# Net500.net
KiCad netlist of a schematic drawn in Altium Designer
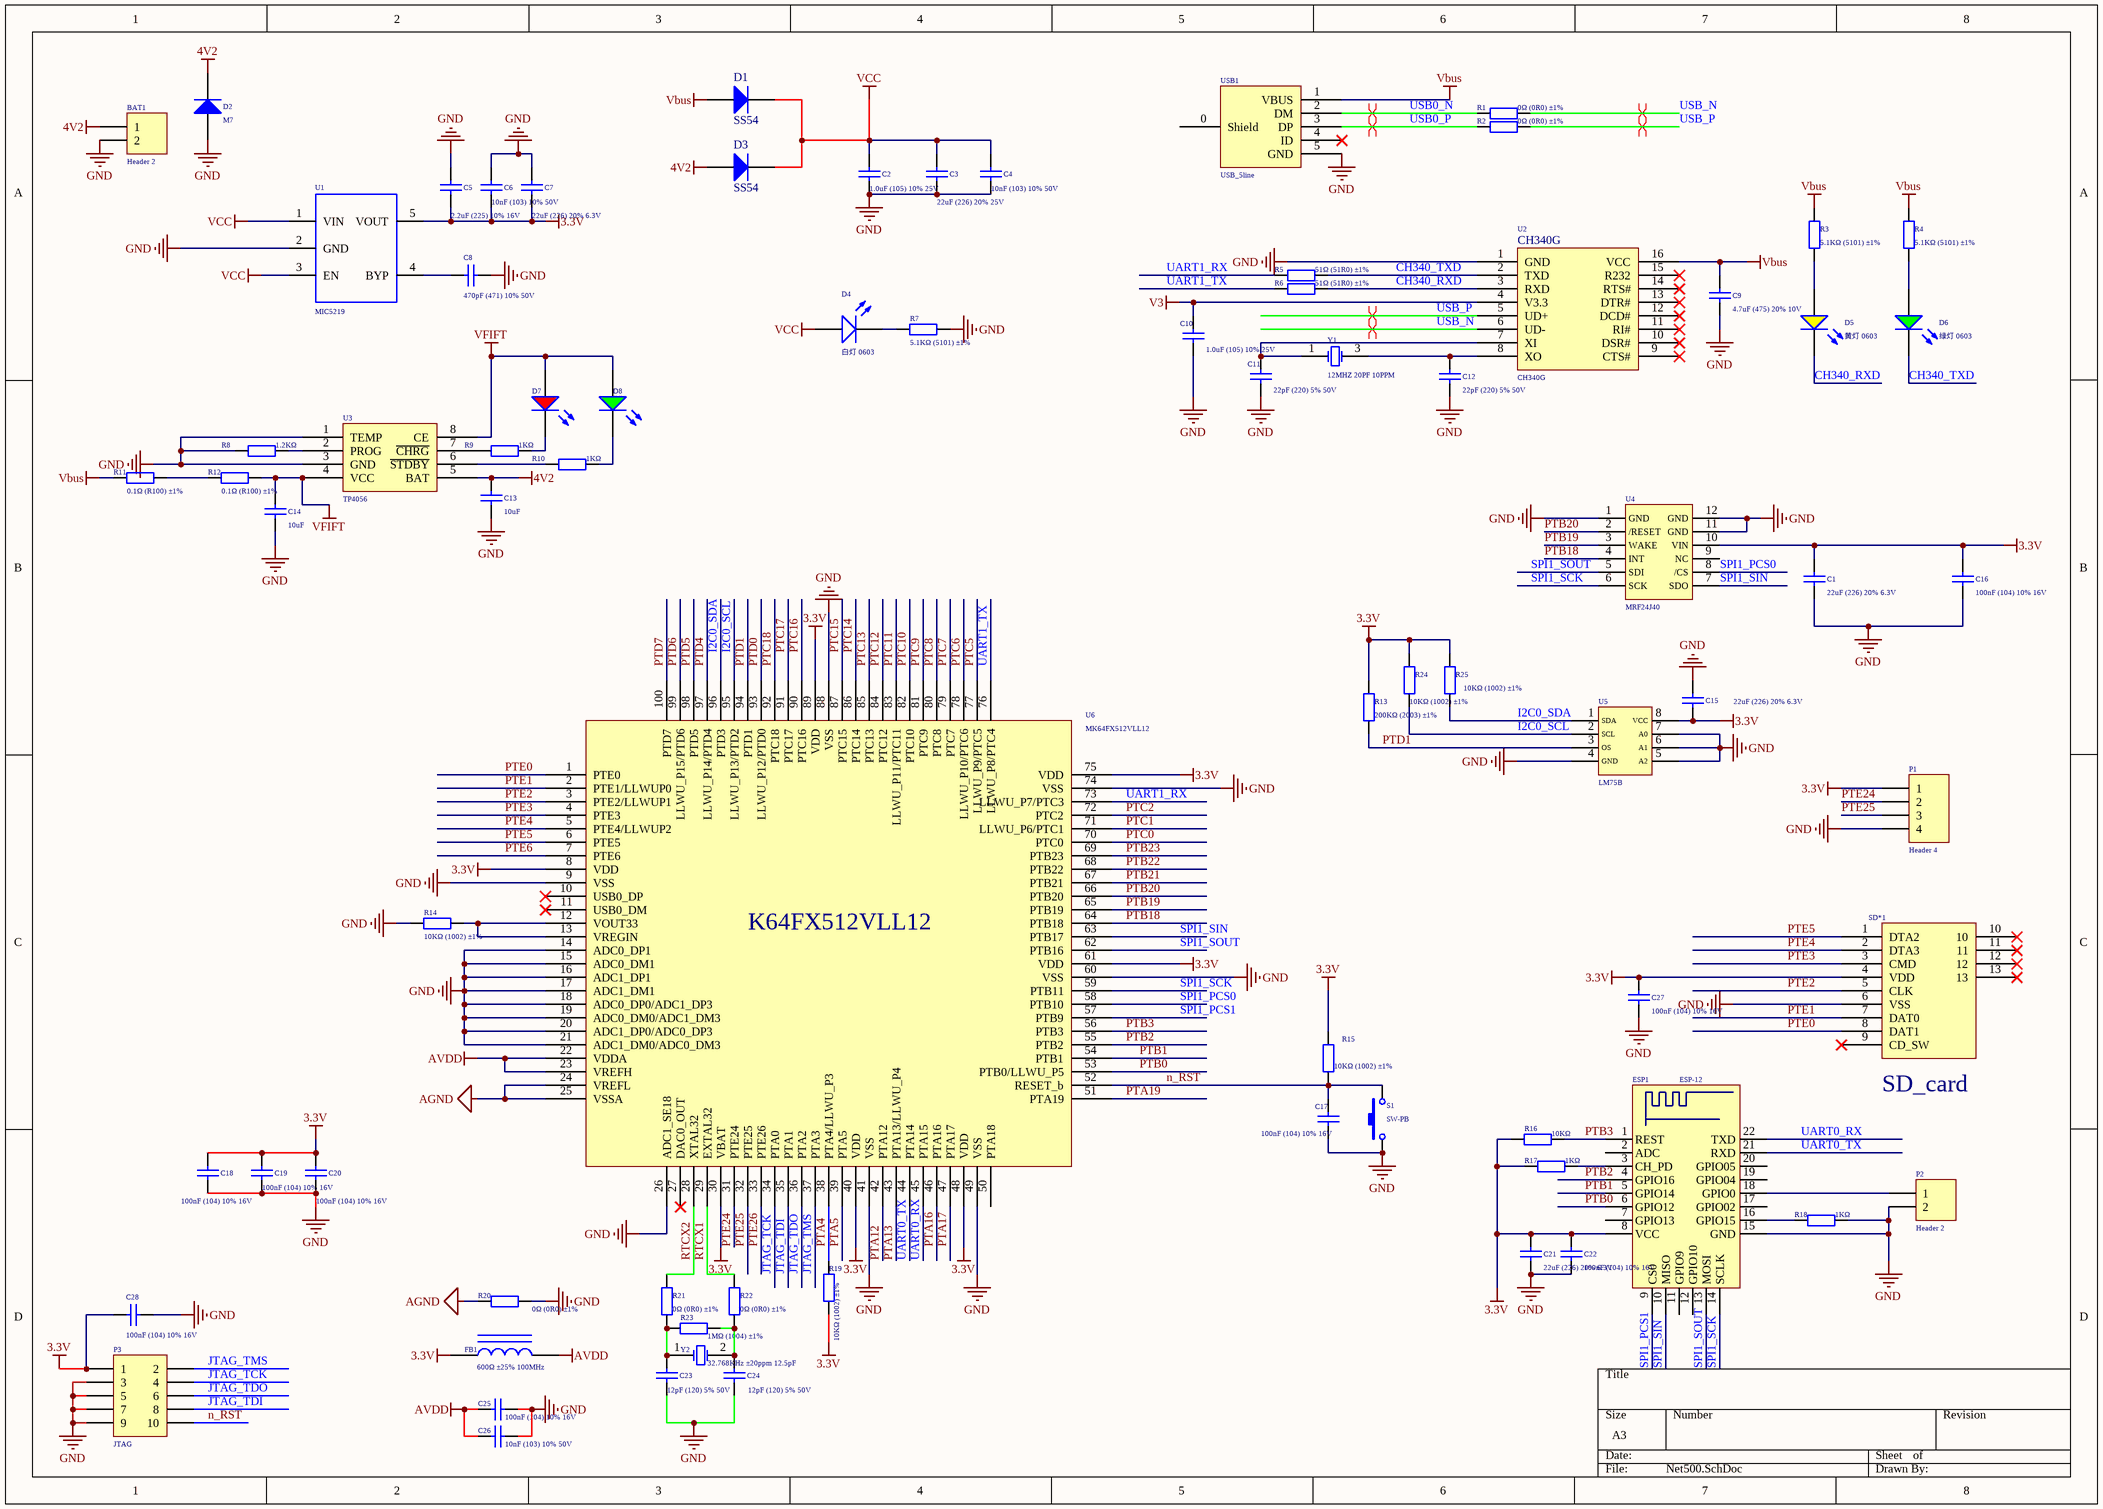
[diagram p0: Net500.SchDoc]

(export (version "E")
  (design (tool "Eeschema 10.0.6"))
  (components
    (comp (ref "BAT1")
      (value "Header 2")
      (footprint "HDR1X2")
      (description "Header, 2-Pin")
      (fields (field (name "PUBLISHER") "Altium Limited"))
      (libsource (lib "Sparks") (part "Header 2"))
    )
    (comp (ref "C1")
      (value "22uF (226) 20% 6.3V")
      (footprint "0603_C")
      (description "贴片电容")
      (libsource (lib "Miscellaneous Devices LC") (part "0603 22uF (226) 20% 6.3V"))
    )
    (comp (ref "C2")
      (value "1.0uF (105) 10% 25V")
      (footprint "0402_C")
      (description "贴片电容")
      (libsource (lib "Miscellaneous Devices LC") (part "0402 1.0uF (105) 10% 25V"))
    )
    (comp (ref "C3")
      (value "22uF (226) 20% 25V")
      (footprint "0805_C")
      (description "贴片电容")
      (libsource (lib "Miscellaneous Devices LC") (part "0805 22uF (226) 20% 25V"))
    )
    (comp (ref "C4")
      (value "10nF (103) 10% 50V")
      (footprint "0402_C")
      (description "贴片电容")
      (libsource (lib "Miscellaneous Devices LC") (part "0402 10nF (103) 10% 50V"))
    )
    (comp (ref "C5")
      (value "2.2uF (225) 10% 16V")
      (footprint "0603_C")
      (description "贴片电容")
      (libsource (lib "Miscellaneous Devices LC") (part "0603 2.2uF (225) 10% 16V"))
    )
    (comp (ref "C6")
      (value "10nF (103) 10% 50V")
      (footprint "0402_C")
      (description "贴片电容")
      (libsource (lib "Miscellaneous Devices LC") (part "0402 10nF (103) 10% 50V"))
    )
    (comp (ref "C7")
      (value "22uF (226) 20% 6.3V")
      (footprint "0603_C")
      (description "贴片电容")
      (libsource (lib "Miscellaneous Devices LC") (part "0603 22uF (226) 20% 6.3V"))
    )
    (comp (ref "C8")
      (value "470pF (471) 10% 50V")
      (footprint "0402_C")
      (description "贴片电容")
      (libsource (lib "Miscellaneous Devices LC") (part "0402 470pF (471) 10% 50V"))
    )
    (comp (ref "C9")
      (value "4.7uF (475) 20% 10V")
      (footprint "0402_C")
      (description "贴片电容")
      (libsource (lib "Miscellaneous Devices LC") (part "0402 4.7uF (475) 20% 10V"))
    )
    (comp (ref "C10")
      (value "1.0uF (105) 10% 25V")
      (footprint "0402_C")
      (description "贴片电容")
      (libsource (lib "Miscellaneous Devices LC") (part "0402 1.0uF (105) 10% 25V"))
    )
    (comp (ref "C11")
      (value "22pF (220) 5% 50V")
      (footprint "0402_C")
      (description "贴片电容")
      (libsource (lib "Miscellaneous Devices LC") (part "0402 22pF (220) 5% 50V"))
    )
    (comp (ref "C12")
      (value "22pF (220) 5% 50V")
      (footprint "0402_C")
      (description "贴片电容")
      (libsource (lib "Miscellaneous Devices LC") (part "0402 22pF (220) 5% 50V"))
    )
    (comp (ref "C13")
      (value "10uF")
      (footprint "0402_C")
      (description "贴片电容")
      (libsource (lib "Cap") (part "0402 10uF (106) 20% 6.3V"))
    )
    (comp (ref "C14")
      (value "10uF")
      (footprint "0402_C")
      (description "贴片电容")
      (libsource (lib "Cap") (part "0402 10uF (106) 20% 6.3V"))
    )
    (comp (ref "C15")
      (value "22uF (226) 20% 6.3V")
      (footprint "0603_C")
      (description "贴片电容")
      (libsource (lib "Miscellaneous Devices LC") (part "0603 22uF (226) 20% 6.3V"))
    )
    (comp (ref "C16")
      (value "100nF (104) 10% 16V")
      (footprint "0402_C")
      (description "贴片电容")
      (libsource (lib "Miscellaneous Devices LC") (part "0402 100nF (104) 10% 16V"))
    )
    (comp (ref "C17")
      (value "100nF (104) 10% 16V")
      (footprint "0402_C")
      (description "贴片电容")
      (libsource (lib "Miscellaneous Devices LC") (part "0402 100nF (104) 10% 16V"))
    )
    (comp (ref "C18")
      (value "100nF (104) 10% 16V")
      (footprint "0402_C")
      (description "贴片电容")
      (libsource (lib "Miscellaneous Devices LC") (part "0402 100nF (104) 10% 16V"))
    )
    (comp (ref "C19")
      (value "100nF (104) 10% 16V")
      (footprint "0402_C")
      (description "贴片电容")
      (libsource (lib "Miscellaneous Devices LC") (part "0402 100nF (104) 10% 16V"))
    )
    (comp (ref "C20")
      (value "100nF (104) 10% 16V")
      (footprint "0402_C")
      (description "贴片电容")
      (libsource (lib "Miscellaneous Devices LC") (part "0402 100nF (104) 10% 16V"))
    )
    (comp (ref "C21")
      (value "22uF (226) 20% 6.3V")
      (footprint "0603_C")
      (description "贴片电容")
      (libsource (lib "Miscellaneous Devices LC") (part "0603 22uF (226) 20% 6.3V"))
    )
    (comp (ref "C22")
      (value "100nF (104) 10% 16V")
      (footprint "0402_C")
      (description "贴片电容")
      (libsource (lib "Miscellaneous Devices LC") (part "0402 100nF (104) 10% 16V"))
    )
    (comp (ref "C23")
      (value "12pF (120) 5% 50V")
      (footprint "0402_C")
      (description "贴片电容")
      (libsource (lib "Miscellaneous Devices LC") (part "0402 12pF (120) 5% 50V"))
    )
    (comp (ref "C24")
      (value "12pF (120) 5% 50V")
      (footprint "0402_C")
      (description "贴片电容")
      (libsource (lib "Miscellaneous Devices LC") (part "0402 12pF (120) 5% 50V"))
    )
    (comp (ref "C25")
      (value "100nF (104) 10% 16V")
      (footprint "0402_C")
      (description "贴片电容")
      (libsource (lib "Miscellaneous Devices LC") (part "0402 100nF (104) 10% 16V"))
    )
    (comp (ref "C26")
      (value "10nF (103) 10% 50V")
      (footprint "0402_C")
      (description "贴片电容")
      (libsource (lib "Miscellaneous Devices LC") (part "0402 10nF (103) 10% 50V"))
    )
    (comp (ref "C27")
      (value "100nF (104) 10% 16V")
      (footprint "0402_C")
      (description "贴片电容")
      (libsource (lib "Miscellaneous Devices LC") (part "0402 100nF (104) 10% 16V"))
    )
    (comp (ref "C28")
      (value "100nF (104) 10% 16V")
      (footprint "0402_C")
      (description "贴片电容")
      (libsource (lib "Miscellaneous Devices LC") (part "0402 100nF (104) 10% 16V"))
    )
    (comp (ref "D1")
      (value "SS54")
      (footprint "SMA(DO-214AC)_S1")
      (description "二极管")
      (libsource (lib "Miscellaneous Devices LC") (part "SMA(DO-214AC) SS54"))
    )
    (comp (ref "D2")
      (value "M7")
      (footprint "SMA(DO-214AC)_S1")
      (description "二极管")
      (libsource (lib "Miscellaneous Devices LC") (part "SMA(DO-214AC) M7"))
    )
    (comp (ref "D3")
      (value "SS54")
      (footprint "SMA(DO-214AC)_S1")
      (description "二极管")
      (libsource (lib "Miscellaneous Devices LC") (part "SMA(DO-214AC) SS54"))
    )
    (comp (ref "D4")
      (value "白灯 0603")
      (footprint "0603_LED_S1")
      (description "发光二极管")
      (libsource (lib "Miscellaneous Devices LC") (part "0603 白灯"))
    )
    (comp (ref "D5")
      (value "黄灯 0603")
      (footprint "0603_LED_S1")
      (description "发光二极管")
      (libsource (lib "Miscellaneous Devices LC") (part "0603 黄灯"))
    )
    (comp (ref "D6")
      (value "绿灯 0603")
      (footprint "0603_LED_S1")
      (description "发光二极管")
      (libsource (lib "Miscellaneous Devices LC") (part "0603 绿灯"))
    )
    (comp (ref "D7")
      (value "红灯 0603")
      (footprint "0603_LED_S1")
      (description "发光二极管")
      (libsource (lib "LED") (part "0603 红灯"))
    )
    (comp (ref "D8")
      (value "绿灯 0603")
      (footprint "0603_LED_S1")
      (description "发光二极管")
      (libsource (lib "LED") (part "0603 绿灯"))
    )
    (comp (ref "ESP1") (value "ESP-12") (footprint "ESP-12") (libsource (lib "2号库") (part "ESP-12")))
    (comp (ref "FB1")
      (value "600Ω ±25% 100MHz")
      (footprint "0805_L")
      (description "贴片磁珠")
      (libsource (lib "Miscellaneous Devices LC") (part "0805 600Ω 25% 100MHz"))
    )
    (comp (ref "P1")
      (value "Header 4")
      (footprint "HDR1X4")
      (description "Header, 4-Pin")
      (fields (field (name "PUBLISHER") "Altium Limited"))
      (libsource (lib "Sparks") (part "Header 4"))
    )
    (comp (ref "P2")
      (value "Header 2")
      (footprint "HDR1X2")
      (description "Header, 2-Pin")
      (fields (field (name "PUBLISHER") "Altium Limited"))
      (libsource (lib "Sparks") (part "Header 2"))
    )
    (comp (ref "P3")
      (value "JTAG")
      (footprint "MHDR2X5")
      (description "Header, 5-Pin, Dual row")
      (fields (field (name "PUBLISHER") "Altium Limited"))
      (libsource (lib "Sparks") (part "Header 5X2"))
    )
    (comp (ref "R1")
      (value "0Ω (0R0) ±1%")
      (footprint "0402_R")
      (description "贴片电阻")
      (libsource (lib "") (part "0402 0Ω (0R0) 1%_1"))
    )
    (comp (ref "R2")
      (value "0Ω (0R0) ±1%")
      (footprint "0402_R")
      (description "贴片电阻")
      (libsource (lib "") (part "0402 0Ω (0R0) 1%_1"))
    )
    (comp (ref "R3")
      (value "5.1KΩ (5101) ±1%")
      (footprint "0402_R")
      (description "贴片电阻")
      (libsource (lib "Miscellaneous Devices LC") (part "0402 5.1KΩ (5101) 1%"))
    )
    (comp (ref "R4")
      (value "5.1KΩ (5101) ±1%")
      (footprint "0402_R")
      (description "贴片电阻")
      (libsource (lib "Miscellaneous Devices LC") (part "0402 5.1KΩ (5101) 1%"))
    )
    (comp (ref "R5")
      (value "51Ω (51R0) ±1%")
      (footprint "0402_R")
      (description "贴片电阻")
      (libsource (lib "Miscellaneous Devices LC") (part "0402 51Ω (51R0) 1%"))
    )
    (comp (ref "R6")
      (value "51Ω (51R0) ±1%")
      (footprint "0402_R")
      (description "贴片电阻")
      (libsource (lib "Miscellaneous Devices LC") (part "0402 51Ω (51R0) 1%"))
    )
    (comp (ref "R7")
      (value "5.1KΩ (5101) ±1%")
      (footprint "0402_R")
      (description "贴片电阻")
      (libsource (lib "") (part "0402 5.1KΩ (5101) 1%_1"))
    )
    (comp (ref "R8")
      (value "1.2KΩ")
      (footprint "0402_R")
      (description "贴片电阻")
      (libsource (lib "RES") (part "0402 1.2KΩ (1201) 1%"))
    )
    (comp (ref "R9")
      (value "1KΩ")
      (footprint "0402_R")
      (description "贴片电阻")
      (libsource (lib "RES") (part "0402 1KΩ (1001) 1%"))
    )
    (comp (ref "R10")
      (value "1KΩ")
      (footprint "0402_R")
      (description "贴片电阻")
      (libsource (lib "RES") (part "0402 1KΩ (1001) 1%"))
    )
    (comp (ref "R11")
      (value "0.1Ω (R100) ±1%")
      (footprint "1206_R")
      (description "贴片电阻")
      (libsource (lib "Miscellaneous Devices LC") (part "1206 0.1Ω (R100) 1%"))
    )
    (comp (ref "R12")
      (value "0.1Ω (R100) ±1%")
      (footprint "1206_R")
      (description "贴片电阻")
      (libsource (lib "Miscellaneous Devices LC") (part "1206 0.1Ω (R100) 1%"))
    )
    (comp (ref "R13")
      (value "200KΩ (2003) ±1%")
      (footprint "0402_R")
      (description "贴片电阻")
      (libsource (lib "Miscellaneous Devices LC") (part "0402 200KΩ (2003) 1%"))
    )
    (comp (ref "R14")
      (value "10KΩ (1002) ±1%")
      (footprint "0402_R")
      (description "贴片电阻")
      (libsource (lib "") (part "0402 10KΩ (1002) 1%_1"))
    )
    (comp (ref "R15")
      (value "10KΩ (1002) ±1%")
      (footprint "0402_R")
      (description "贴片电阻")
      (libsource (lib "Miscellaneous Devices LC") (part "0402 10KΩ (1002) 1%"))
    )
    (comp (ref "R16")
      (value "10KΩ")
      (footprint "0603_R")
      (description "贴片电阻")
      (libsource (lib "RES") (part "0603 10KΩ (1002) 1%"))
    )
    (comp (ref "R17")
      (value "1KΩ")
      (footprint "0603_R")
      (description "贴片电阻")
      (libsource (lib "RES") (part "0603 1KΩ (1001) 1%"))
    )
    (comp (ref "R18")
      (value "1KΩ")
      (footprint "0603_R")
      (description "贴片电阻")
      (libsource (lib "RES") (part "0603 1KΩ (1001) 1%"))
    )
    (comp (ref "R19")
      (value "10KΩ (1002) ±1%")
      (footprint "0402_R")
      (description "贴片电阻")
      (libsource (lib "Miscellaneous Devices LC") (part "0402 10KΩ (1002) 1%"))
    )
    (comp (ref "R20")
      (value "0Ω (0R0) ±1%")
      (footprint "0402_R")
      (description "贴片电阻")
      (libsource (lib "") (part "0402 0Ω (0R0) 1%_1"))
    )
    (comp (ref "R21")
      (value "0Ω (0R0) ±1%")
      (footprint "0402_R")
      (description "贴片电阻")
      (libsource (lib "Miscellaneous Devices LC") (part "0402 0Ω (0R0) 1%"))
    )
    (comp (ref "R22")
      (value "0Ω (0R0) ±1%")
      (footprint "0402_R")
      (description "贴片电阻")
      (libsource (lib "Miscellaneous Devices LC") (part "0402 0Ω (0R0) 1%"))
    )
    (comp (ref "R23")
      (value "1MΩ (1004) ±1%")
      (footprint "0402_R")
      (description "贴片电阻")
      (libsource (lib "Miscellaneous Devices LC") (part "0402 1MΩ (1004) 1%"))
    )
    (comp (ref "R24")
      (value "10KΩ (1002) ±1%")
      (footprint "0402_R")
      (description "贴片电阻")
      (libsource (lib "Miscellaneous Devices LC") (part "0402 10KΩ (1002) 1%"))
    )
    (comp (ref "R25")
      (value "10KΩ (1002) ±1%")
      (footprint "0402_R")
      (description "贴片电阻")
      (libsource (lib "Miscellaneous Devices LC") (part "0402 10KΩ (1002) 1%"))
    )
    (comp (ref "S1")
      (value "SW-PB")
      (footprint "key 3*4*2")
      (description "Switch")
      (libsource (lib "K60-V4.0") (part "SW-PB"))
    )
    (comp (ref "SD*1") (value "TF_card") (footprint "TF卡座(短体)") (libsource (lib "2号库") (part "TF_card")))
    (comp (ref "U1")
      (value "MIC5219")
      (footprint "SOT-23-5")
      (description "LDO")
      (libsource (lib "K60-V4.0") (part "MIC5219"))
    )
    (comp (ref "U2")
      (value "CH340G")
      (footprint "SOIC-16_150mil")
      (description "USB")
      (libsource (lib "Miscellaneous Devices LC") (part "CH340G_[C14267]"))
    )
    (comp (ref "U3")
      (value "TP4056")
      (footprint "SOP-8_EP_150mil")
      (description "电池电源管理")
      (libsource (lib "IC") (part "TP4056_[C16581]"))
    )
    (comp (ref "U4") (value "MRF24J40") (footprint "MRF24J40") (libsource (lib "2号库") (part "MRF24J40")))
    (comp (ref "U5")
      (value "LM75B")
      (footprint "LC-SOIC-8_150mil")
      (libsource (lib "jlcUser") (part "LM75B"))
    )
    (comp (ref "U6")
      (value "MK64FX512VLL12")
      (footprint "LC-LQFP-100_14x14x05P")
      (libsource (lib "jlcUser") (part "MK64FX512VLL12"))
    )
    (comp (ref "USB1")
      (value "USB_5line")
      (footprint "USB-MICRO-5P-2F")
      (libsource (lib "2号库") (part "USB_5line"))
    )
    (comp (ref "Y1")
      (value "12MHZ 20PF 10PPM")
      (footprint "SMD-3225_4P")
      (description "贴片晶振")
      (libsource (lib "Miscellaneous Devices LC") (part "SMD-3225_4P  12MHZ 20PF 10PPM"))
    )
    (comp (ref "Y2")
      (value "32.768KHz ±20ppm 12.5pF")
      (footprint "SMD-3215_2P FC - 135")
      (description "贴片晶振")
      (libsource (lib "Miscellaneous Devices LC") (part "SMD-3215_2P 32.768KHz 20ppm 12.5pF"))
    )
  )
  (nets
    (net (code "1") (name "/CH340_RXD") (class "Default")
      (node (ref "D5") (pin "K") (pinfunction "K_K") (pintype "passive"))
      (node (ref "R6") (pin "2") (pinfunction "2_2") (pintype "passive"))
      (node (ref "U2") (pin "3") (pinfunction "RXD_3") (pintype "passive"))
    )
    (net (code "2") (name "/CH340_TXD") (class "Default")
      (node (ref "D6") (pin "K") (pinfunction "K_K") (pintype "passive"))
      (node (ref "R5") (pin "2") (pinfunction "2_2") (pintype "passive"))
      (node (ref "U2") (pin "2") (pinfunction "TXD_2") (pintype "passive"))
    )
    (net (code "3") (name "/I2C0_SCL") (class "Default")
      (node (ref "R24") (pin "1") (pinfunction "1_1") (pintype "passive"))
      (node (ref "U5") (pin "2") (pinfunction "SCL_2") (pintype "passive"))
      (node (ref "U6") (pin "95") (pinfunction "LLWU_P13/PTD2_95") (pintype "passive"))
    )
    (net (code "4") (name "/I2C0_SDA") (class "Default")
      (node (ref "R25") (pin "1") (pinfunction "1_1") (pintype "passive"))
      (node (ref "U5") (pin "1") (pinfunction "SDA_1") (pintype "passive"))
      (node (ref "U6") (pin "96") (pinfunction "PTD3_96") (pintype "passive"))
    )
    (net (code "5") (name "/JTAG_TCK") (class "Default")
      (node (ref "P3") (pin "4") (pinfunction "4_4") (pintype "passive"))
      (node (ref "U6") (pin "34") (pinfunction "PTA0_34") (pintype "passive"))
    )
    (net (code "6") (name "/JTAG_TDI") (class "Default")
      (node (ref "P3") (pin "8") (pinfunction "8_8") (pintype "passive"))
      (node (ref "U6") (pin "35") (pinfunction "PTA1_35") (pintype "passive"))
    )
    (net (code "7") (name "/JTAG_TDO") (class "Default")
      (node (ref "P3") (pin "6") (pinfunction "6_6") (pintype "passive"))
      (node (ref "U6") (pin "36") (pinfunction "PTA2_36") (pintype "passive"))
    )
    (net (code "8") (name "/JTAG_TMS") (class "Default")
      (node (ref "P3") (pin "2") (pinfunction "2_2") (pintype "passive"))
      (node (ref "U6") (pin "37") (pinfunction "PTA3_37") (pintype "passive"))
    )
    (net (code "9") (name "/PTA4") (class "Default")
      (node (ref "R19") (pin "2") (pinfunction "2_2") (pintype "passive"))
      (node (ref "U6") (pin "38") (pinfunction "PTA4/LLWU_P3_38") (pintype "passive"))
    )
    (net (code "10") (name "/PTA5") (class "Default")
      (node (ref "U6") (pin "39") (pinfunction "PTA5_39") (pintype "passive"))
    )
    (net (code "11") (name "/PTA12") (class "Default")
      (node (ref "U6") (pin "42") (pinfunction "PTA12_42") (pintype "passive"))
    )
    (net (code "12") (name "/PTA13") (class "Default")
      (node (ref "U6") (pin "43") (pinfunction "PTA13/LLWU_P4_43") (pintype "passive"))
    )
    (net (code "13") (name "/PTA16") (class "Default")
      (node (ref "U6") (pin "46") (pinfunction "PTA16_46") (pintype "passive"))
    )
    (net (code "14") (name "/PTA17") (class "Default")
      (node (ref "U6") (pin "47") (pinfunction "PTA17_47") (pintype "passive"))
    )
    (net (code "15") (name "/PTA19") (class "Default")
      (node (ref "U6") (pin "51") (pinfunction "PTA19_51") (pintype "passive"))
    )
    (net (code "16") (name "/PTB0") (class "Default")
      (node (ref "ESP1") (pin "6") (pinfunction "GPIO12_6") (pintype "passive"))
      (node (ref "U6") (pin "53") (pinfunction "PTB0/LLWU_P5_53") (pintype "passive"))
    )
    (net (code "17") (name "/PTB1") (class "Default")
      (node (ref "ESP1") (pin "5") (pinfunction "GPIO14_5") (pintype "passive"))
      (node (ref "U6") (pin "54") (pinfunction "PTB1_54") (pintype "passive"))
    )
    (net (code "18") (name "/PTB2") (class "Default")
      (node (ref "ESP1") (pin "4") (pinfunction "GPIO16_4") (pintype "passive"))
      (node (ref "U6") (pin "55") (pinfunction "PTB2_55") (pintype "passive"))
    )
    (net (code "19") (name "/PTB3") (class "Default")
      (node (ref "ESP1") (pin "1") (pinfunction "REST_1") (pintype "passive"))
      (node (ref "R16") (pin "2") (pinfunction "2_2") (pintype "passive"))
      (node (ref "U6") (pin "56") (pinfunction "PTB3_56") (pintype "passive"))
    )
    (net (code "20") (name "/PTB18") (class "Default")
      (node (ref "U4") (pin "4") (pinfunction "INT_4") (pintype "passive"))
      (node (ref "U6") (pin "64") (pinfunction "PTB18_64") (pintype "passive"))
    )
    (net (code "21") (name "/PTB19") (class "Default")
      (node (ref "U4") (pin "3") (pinfunction "WAKE_3") (pintype "passive"))
      (node (ref "U6") (pin "65") (pinfunction "PTB19_65") (pintype "passive"))
    )
    (net (code "22") (name "/PTB20") (class "Default")
      (node (ref "U4") (pin "2") (pinfunction "/RESET_2") (pintype "passive"))
      (node (ref "U6") (pin "66") (pinfunction "PTB20_66") (pintype "passive"))
    )
    (net (code "23") (name "/PTB21") (class "Default")
      (node (ref "U6") (pin "67") (pinfunction "PTB21_67") (pintype "passive"))
    )
    (net (code "24") (name "/PTB22") (class "Default")
      (node (ref "U6") (pin "68") (pinfunction "PTB22_68") (pintype "passive"))
    )
    (net (code "25") (name "/PTB23") (class "Default")
      (node (ref "U6") (pin "69") (pinfunction "PTB23_69") (pintype "passive"))
    )
    (net (code "26") (name "/PTC0") (class "Default")
      (node (ref "U6") (pin "70") (pinfunction "PTC0_70") (pintype "passive"))
    )
    (net (code "27") (name "/PTC1") (class "Default")
      (node (ref "U6") (pin "71") (pinfunction "LLWU_P6/PTC1_71") (pintype "passive"))
    )
    (net (code "28") (name "/PTC2") (class "Default")
      (node (ref "U6") (pin "72") (pinfunction "PTC2_72") (pintype "passive"))
    )
    (net (code "29") (name "/PTC5") (class "Default")
      (node (ref "U6") (pin "77") (pinfunction "LLWU_P9/PTC5_77") (pintype "passive"))
    )
    (net (code "30") (name "/PTC6") (class "Default")
      (node (ref "U6") (pin "78") (pinfunction "LLWU_P10/PTC6_78") (pintype "passive"))
    )
    (net (code "31") (name "/PTC7") (class "Default")
      (node (ref "U6") (pin "79") (pinfunction "PTC7_79") (pintype "passive"))
    )
    (net (code "32") (name "/PTC8") (class "Default")
      (node (ref "U6") (pin "80") (pinfunction "PTC8_80") (pintype "passive"))
    )
    (net (code "33") (name "/PTC9") (class "Default")
      (node (ref "U6") (pin "81") (pinfunction "PTC9_81") (pintype "passive"))
    )
    (net (code "34") (name "/PTC10") (class "Default")
      (node (ref "U6") (pin "82") (pinfunction "PTC10_82") (pintype "passive"))
    )
    (net (code "35") (name "/PTC11") (class "Default")
      (node (ref "U6") (pin "83") (pinfunction "LLWU_P11/PTC11_83") (pintype "passive"))
    )
    (net (code "36") (name "/PTC12") (class "Default")
      (node (ref "U6") (pin "84") (pinfunction "PTC12_84") (pintype "passive"))
    )
    (net (code "37") (name "/PTC13") (class "Default")
      (node (ref "U6") (pin "85") (pinfunction "PTC13_85") (pintype "passive"))
    )
    (net (code "38") (name "/PTC14") (class "Default")
      (node (ref "U6") (pin "86") (pinfunction "PTC14_86") (pintype "passive"))
    )
    (net (code "39") (name "/PTC15") (class "Default")
      (node (ref "U6") (pin "87") (pinfunction "PTC15_87") (pintype "passive"))
    )
    (net (code "40") (name "/PTC16") (class "Default")
      (node (ref "U6") (pin "90") (pinfunction "PTC16_90") (pintype "passive"))
    )
    (net (code "41") (name "/PTC17") (class "Default")
      (node (ref "U6") (pin "91") (pinfunction "PTC17_91") (pintype "passive"))
    )
    (net (code "42") (name "/PTC18") (class "Default")
      (node (ref "U6") (pin "92") (pinfunction "PTC18_92") (pintype "passive"))
    )
    (net (code "43") (name "/PTD0") (class "Default")
      (node (ref "U6") (pin "93") (pinfunction "LLWU_P12/PTD0_93") (pintype "passive"))
    )
    (net (code "44") (name "/PTD1") (class "Default")
      (node (ref "R13") (pin "1") (pinfunction "1_1") (pintype "passive"))
      (node (ref "U5") (pin "3") (pinfunction "OS_3") (pintype "passive"))
      (node (ref "U6") (pin "94") (pinfunction "PTD1_94") (pintype "passive"))
    )
    (net (code "45") (name "/PTD4") (class "Default")
      (node (ref "U6") (pin "97") (pinfunction "LLWU_P14/PTD4_97") (pintype "passive"))
    )
    (net (code "46") (name "/PTD5") (class "Default")
      (node (ref "U6") (pin "98") (pinfunction "PTD5_98") (pintype "passive"))
    )
    (net (code "47") (name "/PTD6") (class "Default")
      (node (ref "U6") (pin "99") (pinfunction "LLWU_P15/PTD6_99") (pintype "passive"))
    )
    (net (code "48") (name "/PTD7") (class "Default")
      (node (ref "U6") (pin "100") (pinfunction "PTD7_100") (pintype "passive"))
    )
    (net (code "49") (name "/PTE0") (class "Default")
      (node (ref "SD*1") (pin "8") (pinfunction "DAT1_8") (pintype "passive"))
      (node (ref "U6") (pin "1") (pinfunction "PTE0_1") (pintype "passive"))
    )
    (net (code "50") (name "/PTE1") (class "Default")
      (node (ref "SD*1") (pin "7") (pinfunction "DAT0_7") (pintype "passive"))
      (node (ref "U6") (pin "2") (pinfunction "PTE1/LLWUP0_2") (pintype "passive"))
    )
    (net (code "51") (name "/PTE2") (class "Default")
      (node (ref "SD*1") (pin "5") (pinfunction "CLK_5") (pintype "passive"))
      (node (ref "U6") (pin "3") (pinfunction "PTE2/LLWUP1_3") (pintype "passive"))
    )
    (net (code "52") (name "/PTE3") (class "Default")
      (node (ref "SD*1") (pin "3") (pinfunction "CMD_3") (pintype "passive"))
      (node (ref "U6") (pin "4") (pinfunction "PTE3_4") (pintype "passive"))
    )
    (net (code "53") (name "/PTE4") (class "Default")
      (node (ref "SD*1") (pin "2") (pinfunction "DTA3_2") (pintype "passive"))
      (node (ref "U6") (pin "5") (pinfunction "PTE4/LLWUP2_5") (pintype "passive"))
    )
    (net (code "54") (name "/PTE5") (class "Default")
      (node (ref "SD*1") (pin "1") (pinfunction "DTA2_1") (pintype "passive"))
      (node (ref "U6") (pin "6") (pinfunction "PTE5_6") (pintype "passive"))
    )
    (net (code "55") (name "/PTE6") (class "Default")
      (node (ref "U6") (pin "7") (pinfunction "PTE6_7") (pintype "passive"))
    )
    (net (code "56") (name "/PTE24") (class "Default")
      (node (ref "P1") (pin "2") (pinfunction "2_2") (pintype "passive"))
      (node (ref "U6") (pin "31") (pinfunction "PTE24_31") (pintype "passive"))
    )
    (net (code "57") (name "/PTE25") (class "Default")
      (node (ref "P1") (pin "3") (pinfunction "3_3") (pintype "passive"))
      (node (ref "U6") (pin "32") (pinfunction "PTE25_32") (pintype "passive"))
    )
    (net (code "58") (name "/PTE26") (class "Default")
      (node (ref "U6") (pin "33") (pinfunction "PTE26_33") (pintype "passive"))
    )
    (net (code "59") (name "/RTCX1") (class "Default")
      (node (ref "R22") (pin "2") (pinfunction "2_2") (pintype "passive"))
      (node (ref "U6") (pin "29") (pinfunction "EXTAL32_29") (pintype "passive"))
    )
    (net (code "60") (name "/RTCX2") (class "Default")
      (node (ref "R21") (pin "2") (pinfunction "2_2") (pintype "passive"))
      (node (ref "U6") (pin "28") (pinfunction "XTAL32_28") (pintype "passive"))
    )
    (net (code "61") (name "/SPI1_PCS0") (class "Default")
      (node (ref "U4") (pin "8") (pinfunction "/CS_8") (pintype "passive"))
      (node (ref "U6") (pin "58") (pinfunction "PTB10_58") (pintype "passive"))
    )
    (net (code "62") (name "/SPI1_PCS1") (class "Default")
      (node (ref "ESP1") (pin "9") (pinfunction "CS0_9") (pintype "passive"))
      (node (ref "U6") (pin "57") (pinfunction "PTB9_57") (pintype "passive"))
    )
    (net (code "63") (name "/SPI1_SCK") (class "Default")
      (node (ref "ESP1") (pin "14") (pinfunction "SCLK_14") (pintype "passive"))
      (node (ref "U4") (pin "6") (pinfunction "SCK_6") (pintype "passive"))
      (node (ref "U6") (pin "59") (pinfunction "PTB11_59") (pintype "passive"))
    )
    (net (code "64") (name "/SPI1_SIN") (class "Default")
      (node (ref "ESP1") (pin "10") (pinfunction "MISO_10") (pintype "passive"))
      (node (ref "U4") (pin "7") (pinfunction "SDO_7") (pintype "passive"))
      (node (ref "U6") (pin "63") (pinfunction "PTB17_63") (pintype "passive"))
    )
    (net (code "65") (name "/SPI1_SOUT") (class "Default")
      (node (ref "ESP1") (pin "13") (pinfunction "MOSI_13") (pintype "passive"))
      (node (ref "U4") (pin "5") (pinfunction "SDI_5") (pintype "passive"))
      (node (ref "U6") (pin "62") (pinfunction "PTB16_62") (pintype "passive"))
    )
    (net (code "66") (name "/UART0_RX") (class "Default")
      (node (ref "ESP1") (pin "22") (pinfunction "TXD_22") (pintype "passive"))
      (node (ref "U6") (pin "45") (pinfunction "PTA15_45") (pintype "passive"))
    )
    (net (code "67") (name "/UART0_TX") (class "Default")
      (node (ref "ESP1") (pin "21") (pinfunction "RXD_21") (pintype "passive"))
      (node (ref "U6") (pin "44") (pinfunction "PTA14_44") (pintype "passive"))
    )
    (net (code "68") (name "/UART1_RX") (class "Default")
      (node (ref "R5") (pin "1") (pinfunction "1_1") (pintype "passive"))
      (node (ref "U6") (pin "73") (pinfunction "LLWU_P7/PTC3_73") (pintype "passive"))
    )
    (net (code "69") (name "/UART1_TX") (class "Default")
      (node (ref "R6") (pin "1") (pinfunction "1_1") (pintype "passive"))
      (node (ref "U6") (pin "76") (pinfunction "LLWU_P8/PTC4_76") (pintype "passive"))
    )
    (net (code "70") (name "/USB0_N") (class "Default")
      (node (ref "R1") (pin "1") (pinfunction "1_1") (pintype "passive"))
      (node (ref "USB1") (pin "2") (pinfunction "DM_2") (pintype "passive"))
    )
    (net (code "71") (name "/USB0_P") (class "Default")
      (node (ref "R2") (pin "1") (pinfunction "1_1") (pintype "passive"))
      (node (ref "USB1") (pin "3") (pinfunction "DP_3") (pintype "passive"))
    )
    (net (code "72") (name "/USB_N") (class "Default")
      (node (ref "R1") (pin "2") (pinfunction "2_2") (pintype "passive"))
      (node (ref "U2") (pin "6") (pinfunction "UD-_6") (pintype "passive"))
    )
    (net (code "73") (name "/USB_P") (class "Default")
      (node (ref "R2") (pin "2") (pinfunction "2_2") (pintype "passive"))
      (node (ref "U2") (pin "5") (pinfunction "UD+_5") (pintype "passive"))
    )
    (net (code "74") (name "/n_RST") (class "Default")
      (node (ref "C17") (pin "2") (pinfunction "2_2") (pintype "passive"))
      (node (ref "P3") (pin "10") (pinfunction "10_10") (pintype "passive"))
      (node (ref "R15") (pin "1") (pinfunction "1_1") (pintype "passive"))
      (node (ref "S1") (pin "2") (pinfunction "2_2") (pintype "passive"))
      (node (ref "U6") (pin "52") (pinfunction "RESET_b_52") (pintype "passive"))
    )
    (net (code "75") (name "3.3V") (class "Default")
      (node (ref "C1") (pin "2") (pinfunction "2_2") (pintype "passive"))
      (node (ref "C15") (pin "1") (pinfunction "1_1") (pintype "passive"))
      (node (ref "C16") (pin "2") (pinfunction "2_2") (pintype "passive"))
      (node (ref "C18") (pin "2") (pinfunction "2_2") (pintype "passive"))
      (node (ref "C19") (pin "2") (pinfunction "2_2") (pintype "passive"))
      (node (ref "C20") (pin "2") (pinfunction "2_2") (pintype "passive"))
      (node (ref "C21") (pin "2") (pinfunction "2_2") (pintype "passive"))
      (node (ref "C22") (pin "2") (pinfunction "2_2") (pintype "passive"))
      (node (ref "C27") (pin "2") (pinfunction "2_2") (pintype "passive"))
      (node (ref "C28") (pin "1") (pinfunction "1_1") (pintype "passive"))
      (node (ref "C5") (pin "1") (pinfunction "1_1") (pintype "passive"))
      (node (ref "C6") (pin "1") (pinfunction "1_1") (pintype "passive"))
      (node (ref "C7") (pin "1") (pinfunction "1_1") (pintype "passive"))
      (node (ref "ESP1") (pin "8") (pinfunction "VCC_8") (pintype "passive"))
      (node (ref "FB1") (pin "1") (pinfunction "1_1") (pintype "passive"))
      (node (ref "P1") (pin "1") (pinfunction "1_1") (pintype "passive"))
      (node (ref "P3") (pin "1") (pinfunction "1_1") (pintype "passive"))
      (node (ref "R13") (pin "2") (pinfunction "2_2") (pintype "passive"))
      (node (ref "R15") (pin "2") (pinfunction "2_2") (pintype "passive"))
      (node (ref "R16") (pin "1") (pinfunction "1_1") (pintype "passive"))
      (node (ref "R17") (pin "1") (pinfunction "1_1") (pintype "passive"))
      (node (ref "R19") (pin "1") (pinfunction "1_1") (pintype "passive"))
      (node (ref "R24") (pin "2") (pinfunction "2_2") (pintype "passive"))
      (node (ref "R25") (pin "2") (pinfunction "2_2") (pintype "passive"))
      (node (ref "SD*1") (pin "4") (pinfunction "VDD_4") (pintype "passive"))
      (node (ref "U1") (pin "5") (pinfunction "VOUT_5") (pintype "passive"))
      (node (ref "U4") (pin "10") (pinfunction "VIN_10") (pintype "passive"))
      (node (ref "U5") (pin "8") (pinfunction "VCC_8") (pintype "passive"))
      (node (ref "U6") (pin "30") (pinfunction "VBAT_30") (pintype "passive"))
      (node (ref "U6") (pin "40") (pinfunction "VDD_40") (pintype "passive"))
      (node (ref "U6") (pin "48") (pinfunction "VDD_48") (pintype "passive"))
      (node (ref "U6") (pin "61") (pinfunction "VDD_61") (pintype "passive"))
      (node (ref "U6") (pin "75") (pinfunction "VDD_75") (pintype "passive"))
      (node (ref "U6") (pin "8") (pinfunction "VDD_8") (pintype "passive"))
      (node (ref "U6") (pin "89") (pinfunction "VDD_89") (pintype "passive"))
    )
    (net (code "76") (name "4V2") (class "Default")
      (node (ref "BAT1") (pin "1") (pinfunction "1_1") (pintype "passive"))
      (node (ref "C13") (pin "2") (pinfunction "2_2") (pintype "passive"))
      (node (ref "D2") (pin "2") (pinfunction "K_2") (pintype "passive"))
      (node (ref "D3") (pin "1") (pinfunction "A_1") (pintype "passive"))
      (node (ref "U3") (pin "5") (pinfunction "BAT_5") (pintype "passive"))
    )
    (net (code "77") (name "AGND") (class "Default")
      (node (ref "R20") (pin "1") (pinfunction "1_1") (pintype "passive"))
      (node (ref "U6") (pin "24") (pinfunction "VREFL_24") (pintype "passive"))
      (node (ref "U6") (pin "25") (pinfunction "VSSA_25") (pintype "passive"))
    )
    (net (code "78") (name "AVDD") (class "Default")
      (node (ref "C25") (pin "1") (pinfunction "1_1") (pintype "passive"))
      (node (ref "C26") (pin "1") (pinfunction "1_1") (pintype "passive"))
      (node (ref "FB1") (pin "2") (pinfunction "2_2") (pintype "passive"))
      (node (ref "U6") (pin "22") (pinfunction "VDDA_22") (pintype "passive"))
      (node (ref "U6") (pin "23") (pinfunction "VREFH_23") (pintype "passive"))
    )
    (net (code "79") (name "GND") (class "Default")
      (node (ref "BAT1") (pin "2") (pinfunction "2_2") (pintype "passive"))
      (node (ref "C1") (pin "1") (pinfunction "1_1") (pintype "passive"))
      (node (ref "C10") (pin "1") (pinfunction "1_1") (pintype "passive"))
      (node (ref "C11") (pin "1") (pinfunction "1_1") (pintype "passive"))
      (node (ref "C12") (pin "1") (pinfunction "1_1") (pintype "passive"))
      (node (ref "C13") (pin "1") (pinfunction "1_1") (pintype "passive"))
      (node (ref "C14") (pin "1") (pinfunction "1_1") (pintype "passive"))
      (node (ref "C15") (pin "2") (pinfunction "2_2") (pintype "passive"))
      (node (ref "C16") (pin "1") (pinfunction "1_1") (pintype "passive"))
      (node (ref "C17") (pin "1") (pinfunction "1_1") (pintype "passive"))
      (node (ref "C18") (pin "1") (pinfunction "1_1") (pintype "passive"))
      (node (ref "C19") (pin "1") (pinfunction "1_1") (pintype "passive"))
      (node (ref "C2") (pin "1") (pinfunction "1_1") (pintype "passive"))
      (node (ref "C20") (pin "1") (pinfunction "1_1") (pintype "passive"))
      (node (ref "C21") (pin "1") (pinfunction "1_1") (pintype "passive"))
      (node (ref "C22") (pin "1") (pinfunction "1_1") (pintype "passive"))
      (node (ref "C23") (pin "1") (pinfunction "1_1") (pintype "passive"))
      (node (ref "C24") (pin "1") (pinfunction "1_1") (pintype "passive"))
      (node (ref "C25") (pin "2") (pinfunction "2_2") (pintype "passive"))
      (node (ref "C26") (pin "2") (pinfunction "2_2") (pintype "passive"))
      (node (ref "C27") (pin "1") (pinfunction "1_1") (pintype "passive"))
      (node (ref "C28") (pin "2") (pinfunction "2_2") (pintype "passive"))
      (node (ref "C3") (pin "1") (pinfunction "1_1") (pintype "passive"))
      (node (ref "C4") (pin "1") (pinfunction "1_1") (pintype "passive"))
      (node (ref "C5") (pin "2") (pinfunction "2_2") (pintype "passive"))
      (node (ref "C6") (pin "2") (pinfunction "2_2") (pintype "passive"))
      (node (ref "C7") (pin "2") (pinfunction "2_2") (pintype "passive"))
      (node (ref "C8") (pin "2") (pinfunction "2_2") (pintype "passive"))
      (node (ref "C9") (pin "1") (pinfunction "1_1") (pintype "passive"))
      (node (ref "D2") (pin "1") (pinfunction "A_1") (pintype "passive"))
      (node (ref "ESP1") (pin "15") (pinfunction "GND_15") (pintype "passive"))
      (node (ref "P1") (pin "4") (pinfunction "4_4") (pintype "passive"))
      (node (ref "P2") (pin "2") (pinfunction "2_2") (pintype "passive"))
      (node (ref "P3") (pin "3") (pinfunction "3_3") (pintype "passive"))
      (node (ref "P3") (pin "5") (pinfunction "5_5") (pintype "passive"))
      (node (ref "P3") (pin "7") (pinfunction "7_7") (pintype "passive"))
      (node (ref "P3") (pin "9") (pinfunction "9_9") (pintype "passive"))
      (node (ref "R14") (pin "2") (pinfunction "2_2") (pintype "passive"))
      (node (ref "R18") (pin "2") (pinfunction "2_2") (pintype "passive"))
      (node (ref "R20") (pin "2") (pinfunction "2_2") (pintype "passive"))
      (node (ref "R7") (pin "2") (pinfunction "2_2") (pintype "passive"))
      (node (ref "R8") (pin "1") (pinfunction "1_1") (pintype "passive"))
      (node (ref "S1") (pin "1") (pinfunction "1_1") (pintype "passive"))
      (node (ref "SD*1") (pin "6") (pinfunction "VSS_6") (pintype "passive"))
      (node (ref "U1") (pin "2") (pinfunction "GND_2") (pintype "passive"))
      (node (ref "U2") (pin "1") (pinfunction "GND_1") (pintype "passive"))
      (node (ref "U3") (pin "1") (pinfunction "TEMP_1") (pintype "passive"))
      (node (ref "U3") (pin "3") (pinfunction "GND_3") (pintype "passive"))
      (node (ref "U4") (pin "1") (pinfunction "GND_1") (pintype "passive"))
      (node (ref "U4") (pin "11") (pinfunction "GND_11") (pintype "passive"))
      (node (ref "U4") (pin "12") (pinfunction "GND_12") (pintype "passive"))
      (node (ref "U5") (pin "4") (pinfunction "GND_4") (pintype "passive"))
      (node (ref "U5") (pin "5") (pinfunction "A2_5") (pintype "passive"))
      (node (ref "U5") (pin "6") (pinfunction "A1_6") (pintype "passive"))
      (node (ref "U5") (pin "7") (pinfunction "A0_7") (pintype "passive"))
      (node (ref "U6") (pin "14") (pinfunction "ADC0_DP1_14") (pintype "passive"))
      (node (ref "U6") (pin "15") (pinfunction "ADC0_DM1_15") (pintype "passive"))
      (node (ref "U6") (pin "16") (pinfunction "ADC1_DP1_16") (pintype "passive"))
      (node (ref "U6") (pin "17") (pinfunction "ADC1_DM1_17") (pintype "passive"))
      (node (ref "U6") (pin "18") (pinfunction "ADC0_DP0/ADC1_DP3_18") (pintype "passive"))
      (node (ref "U6") (pin "19") (pinfunction "ADC0_DM0/ADC1_DM3_19") (pintype "passive"))
      (node (ref "U6") (pin "20") (pinfunction "ADC1_DP0/ADC0_DP3_20") (pintype "passive"))
      (node (ref "U6") (pin "21") (pinfunction "ADC1_DM0/ADC0_DM3_21") (pintype "passive"))
      (node (ref "U6") (pin "26") (pinfunction "ADC1_SE18_26") (pintype "passive"))
      (node (ref "U6") (pin "41") (pinfunction "VSS_41") (pintype "passive"))
      (node (ref "U6") (pin "49") (pinfunction "VSS_49") (pintype "passive"))
      (node (ref "U6") (pin "60") (pinfunction "VSS_60") (pintype "passive"))
      (node (ref "U6") (pin "74") (pinfunction "VSS_74") (pintype "passive"))
      (node (ref "U6") (pin "88") (pinfunction "VSS_88") (pintype "passive"))
      (node (ref "U6") (pin "9") (pinfunction "VSS_9") (pintype "passive"))
      (node (ref "USB1") (pin "5") (pinfunction "GND_5") (pintype "passive"))
    )
    (net (code "80") (name "Net-(D4-PadK)") (class "Default")
      (node (ref "D4") (pin "K") (pinfunction "K_K") (pintype "passive"))
      (node (ref "R7") (pin "1") (pinfunction "1_1") (pintype "passive"))
    )
    (net (code "81") (name "Net-(D5-PadA)") (class "Default")
      (node (ref "D5") (pin "A") (pinfunction "A_A") (pintype "passive"))
      (node (ref "R3") (pin "1") (pinfunction "1_1") (pintype "passive"))
    )
    (net (code "82") (name "Net-(D6-PadA)") (class "Default")
      (node (ref "D6") (pin "A") (pinfunction "A_A") (pintype "passive"))
      (node (ref "R4") (pin "1") (pinfunction "1_1") (pintype "passive"))
    )
    (net (code "83") (name "Net-(D7-PadK)") (class "Default")
      (node (ref "D7") (pin "K") (pinfunction "K_K") (pintype "passive"))
      (node (ref "R9") (pin "2") (pinfunction "2_2") (pintype "passive"))
    )
    (net (code "84") (name "Net-(D8-PadK)") (class "Default")
      (node (ref "D8") (pin "K") (pinfunction "K_K") (pintype "passive"))
      (node (ref "R10") (pin "2") (pinfunction "2_2") (pintype "passive"))
    )
    (net (code "85") (name "Net-(ESP1-CH_PD)") (class "Default")
      (node (ref "ESP1") (pin "3") (pinfunction "CH_PD_3") (pintype "passive"))
      (node (ref "R17") (pin "2") (pinfunction "2_2") (pintype "passive"))
    )
    (net (code "86") (name "Net-(ESP1-GPIO0)") (class "Default")
      (node (ref "ESP1") (pin "18") (pinfunction "GPIO0_18") (pintype "passive"))
      (node (ref "P2") (pin "1") (pinfunction "1_1") (pintype "passive"))
    )
    (net (code "87") (name "Net-(ESP1-GPIO15)") (class "Default")
      (node (ref "ESP1") (pin "16") (pinfunction "GPIO15_16") (pintype "passive"))
      (node (ref "R18") (pin "1") (pinfunction "1_1") (pintype "passive"))
    )
    (net (code "88") (name "Net-(R11-Pad2)") (class "Default")
      (node (ref "R11") (pin "2") (pinfunction "2_2") (pintype "passive"))
      (node (ref "R12") (pin "1") (pinfunction "1_1") (pintype "passive"))
    )
    (net (code "89") (name "Net-(U1-BYP)") (class "Default")
      (node (ref "C8") (pin "1") (pinfunction "1_1") (pintype "passive"))
      (node (ref "U1") (pin "4") (pinfunction "BYP_4") (pintype "passive"))
    )
    (net (code "90") (name "Net-(U2-XI)") (class "Default")
      (node (ref "C11") (pin "2") (pinfunction "2_2") (pintype "passive"))
      (node (ref "U2") (pin "7") (pinfunction "XI_7") (pintype "passive"))
      (node (ref "Y1") (pin "1") (pinfunction "OSC1_1") (pintype "passive"))
    )
    (net (code "91") (name "Net-(U2-XO)") (class "Default")
      (node (ref "C12") (pin "2") (pinfunction "2_2") (pintype "passive"))
      (node (ref "U2") (pin "8") (pinfunction "XO_8") (pintype "passive"))
      (node (ref "Y1") (pin "3") (pinfunction "OSC2_3") (pintype "passive"))
    )
    (net (code "92") (name "Net-(U3-PROG)") (class "Default")
      (node (ref "R8") (pin "2") (pinfunction "2_2") (pintype "passive"))
      (node (ref "U3") (pin "2") (pinfunction "PROG_2") (pintype "passive"))
    )
    (net (code "93") (name "Net-(U3-~{CHRG})") (class "Default")
      (node (ref "R9") (pin "1") (pinfunction "1_1") (pintype "passive"))
      (node (ref "U3") (pin "7") (pinfunction "~{CHRG}_7") (pintype "passive"))
    )
    (net (code "94") (name "Net-(U3-~{STDBY})") (class "Default")
      (node (ref "R10") (pin "1") (pinfunction "1_1") (pintype "passive"))
      (node (ref "U3") (pin "6") (pinfunction "~{STDBY}_6") (pintype "passive"))
    )
    (net (code "95") (name "Net-(U6-VOUT33)") (class "Default")
      (node (ref "R14") (pin "1") (pinfunction "1_1") (pintype "passive"))
      (node (ref "U6") (pin "12") (pinfunction "VOUT33_12") (pintype "passive"))
      (node (ref "U6") (pin "13") (pinfunction "VREGIN_13") (pintype "passive"))
    )
    (net (code "96") (name "Net-(Y2-OSC1)") (class "Default")
      (node (ref "C23") (pin "2") (pinfunction "2_2") (pintype "passive"))
      (node (ref "R21") (pin "1") (pinfunction "1_1") (pintype "passive"))
      (node (ref "R23") (pin "1") (pinfunction "1_1") (pintype "passive"))
      (node (ref "Y2") (pin "1") (pinfunction "OSC1_1") (pintype "passive"))
    )
    (net (code "97") (name "Net-(Y2-OSC2)") (class "Default")
      (node (ref "C24") (pin "2") (pinfunction "2_2") (pintype "passive"))
      (node (ref "R22") (pin "1") (pinfunction "1_1") (pintype "passive"))
      (node (ref "R23") (pin "2") (pinfunction "2_2") (pintype "passive"))
      (node (ref "Y2") (pin "2") (pinfunction "OSC2_2") (pintype "passive"))
    )
    (net (code "98") (name "V3") (class "Default")
      (node (ref "C10") (pin "2") (pinfunction "2_2") (pintype "passive"))
      (node (ref "U2") (pin "4") (pinfunction "V3.3_4") (pintype "passive"))
    )
    (net (code "99") (name "VCC") (class "Default")
      (node (ref "C2") (pin "2") (pinfunction "2_2") (pintype "passive"))
      (node (ref "C3") (pin "2") (pinfunction "2_2") (pintype "passive"))
      (node (ref "C4") (pin "2") (pinfunction "2_2") (pintype "passive"))
      (node (ref "D1") (pin "2") (pinfunction "K_2") (pintype "passive"))
      (node (ref "D3") (pin "2") (pinfunction "K_2") (pintype "passive"))
      (node (ref "D4") (pin "A") (pinfunction "A_A") (pintype "passive"))
      (node (ref "U1") (pin "1") (pinfunction "VIN_1") (pintype "passive"))
      (node (ref "U1") (pin "3") (pinfunction "EN_3") (pintype "passive"))
    )
    (net (code "100") (name "VFIFT") (class "Default")
      (node (ref "C14") (pin "2") (pinfunction "2_2") (pintype "passive"))
      (node (ref "D7") (pin "A") (pinfunction "A_A") (pintype "passive"))
      (node (ref "D8") (pin "A") (pinfunction "A_A") (pintype "passive"))
      (node (ref "R12") (pin "2") (pinfunction "2_2") (pintype "passive"))
      (node (ref "U3") (pin "4") (pinfunction "VCC_4") (pintype "passive"))
      (node (ref "U3") (pin "8") (pinfunction "CE_8") (pintype "passive"))
    )
    (net (code "101") (name "Vbus") (class "Default")
      (node (ref "C9") (pin "2") (pinfunction "2_2") (pintype "passive"))
      (node (ref "D1") (pin "1") (pinfunction "A_1") (pintype "passive"))
      (node (ref "R11") (pin "1") (pinfunction "1_1") (pintype "passive"))
      (node (ref "R3") (pin "2") (pinfunction "2_2") (pintype "passive"))
      (node (ref "R4") (pin "2") (pinfunction "2_2") (pintype "passive"))
      (node (ref "U2") (pin "16") (pinfunction "VCC_16") (pintype "passive"))
      (node (ref "USB1") (pin "1") (pinfunction "VBUS_1") (pintype "passive"))
    )
    (net (code "102") (name "unconnected-(ESP1-ADC-Pad2)") (class "Default")
      (node (ref "ESP1") (pin "2") (pinfunction "ADC_2") (pintype "passive"))
    )
    (net (code "103") (name "unconnected-(ESP1-GPIO02-Pad17)") (class "Default")
      (node (ref "ESP1") (pin "17") (pinfunction "GPIO02_17") (pintype "passive"))
    )
    (net (code "104") (name "unconnected-(ESP1-GPIO04-Pad19)") (class "Default")
      (node (ref "ESP1") (pin "19") (pinfunction "GPIO04_19") (pintype "passive"))
    )
    (net (code "105") (name "unconnected-(ESP1-GPIO05-Pad20)") (class "Default")
      (node (ref "ESP1") (pin "20") (pinfunction "GPIO05_20") (pintype "passive"))
    )
    (net (code "106") (name "unconnected-(ESP1-GPIO9-Pad11)") (class "Default")
      (node (ref "ESP1") (pin "11") (pinfunction "GPIO9_11") (pintype "passive"))
    )
    (net (code "107") (name "unconnected-(ESP1-GPIO10-Pad12)") (class "Default")
      (node (ref "ESP1") (pin "12") (pinfunction "GPIO10_12") (pintype "passive"))
    )
    (net (code "108") (name "unconnected-(ESP1-GPIO13-Pad7)") (class "Default")
      (node (ref "ESP1") (pin "7") (pinfunction "GPIO13_7") (pintype "passive"))
    )
    (net (code "109") (name "unconnected-(SD*1-CD_SW-Pad9)") (class "Default")
      (node (ref "SD*1") (pin "9") (pinfunction "CD_SW_9") (pintype "passive+no_connect"))
    )
    (net (code "110") (name "unconnected-(SD*1-Pad10)") (class "Default")
      (node (ref "SD*1") (pin "10") (pinfunction "10_10") (pintype "passive+no_connect"))
    )
    (net (code "111") (name "unconnected-(SD*1-Pad11)") (class "Default")
      (node (ref "SD*1") (pin "11") (pinfunction "11_11") (pintype "passive+no_connect"))
    )
    (net (code "112") (name "unconnected-(SD*1-Pad12)") (class "Default")
      (node (ref "SD*1") (pin "12") (pinfunction "12_12") (pintype "passive+no_connect"))
    )
    (net (code "113") (name "unconnected-(SD*1-Pad13)") (class "Default")
      (node (ref "SD*1") (pin "13") (pinfunction "13_13") (pintype "passive+no_connect"))
    )
    (net (code "114") (name "unconnected-(U2-CTS#-Pad9)") (class "Default")
      (node (ref "U2") (pin "9") (pinfunction "CTS#_9") (pintype "passive+no_connect"))
    )
    (net (code "115") (name "unconnected-(U2-DCD#-Pad12)") (class "Default")
      (node (ref "U2") (pin "12") (pinfunction "DCD#_12") (pintype "passive+no_connect"))
    )
    (net (code "116") (name "unconnected-(U2-DSR#-Pad10)") (class "Default")
      (node (ref "U2") (pin "10") (pinfunction "DSR#_10") (pintype "passive+no_connect"))
    )
    (net (code "117") (name "unconnected-(U2-DTR#-Pad13)") (class "Default")
      (node (ref "U2") (pin "13") (pinfunction "DTR#_13") (pintype "passive+no_connect"))
    )
    (net (code "118") (name "unconnected-(U2-R232-Pad15)") (class "Default")
      (node (ref "U2") (pin "15") (pinfunction "R232_15") (pintype "passive+no_connect"))
    )
    (net (code "119") (name "unconnected-(U2-RI#-Pad11)") (class "Default")
      (node (ref "U2") (pin "11") (pinfunction "RI#_11") (pintype "passive+no_connect"))
    )
    (net (code "120") (name "unconnected-(U2-RTS#-Pad14)") (class "Default")
      (node (ref "U2") (pin "14") (pinfunction "RTS#_14") (pintype "passive+no_connect"))
    )
    (net (code "121") (name "unconnected-(U4-NC-Pad9)") (class "Default")
      (node (ref "U4") (pin "9") (pinfunction "NC_9") (pintype "passive"))
    )
    (net (code "122") (name "unconnected-(U6-DAC0_OUT-Pad27)") (class "Default")
      (node (ref "U6") (pin "27") (pinfunction "DAC0_OUT_27") (pintype "passive+no_connect"))
    )
    (net (code "123") (name "unconnected-(U6-PTA18-Pad50)") (class "Default")
      (node (ref "U6") (pin "50") (pinfunction "PTA18_50") (pintype "passive"))
    )
    (net (code "124") (name "unconnected-(U6-USB0_DM-Pad11)") (class "Default")
      (node (ref "U6") (pin "11") (pinfunction "USB0_DM_11") (pintype "passive+no_connect"))
    )
    (net (code "125") (name "unconnected-(U6-USB0_DP-Pad10)") (class "Default")
      (node (ref "U6") (pin "10") (pinfunction "USB0_DP_10") (pintype "passive+no_connect"))
    )
    (net (code "126") (name "unconnected-(USB1-ID-Pad4)") (class "Default")
      (node (ref "USB1") (pin "4") (pinfunction "ID_4") (pintype "passive+no_connect"))
    )
    (net (code "127") (name "unconnected-(USB1-Shield-Pad0)") (class "Default")
      (node (ref "USB1") (pin "0") (pinfunction "Shield_0") (pintype "passive"))
    )
  )
)
